# gps_car_v7.net
KiCad netlist of a schematic drawn in EAGLE
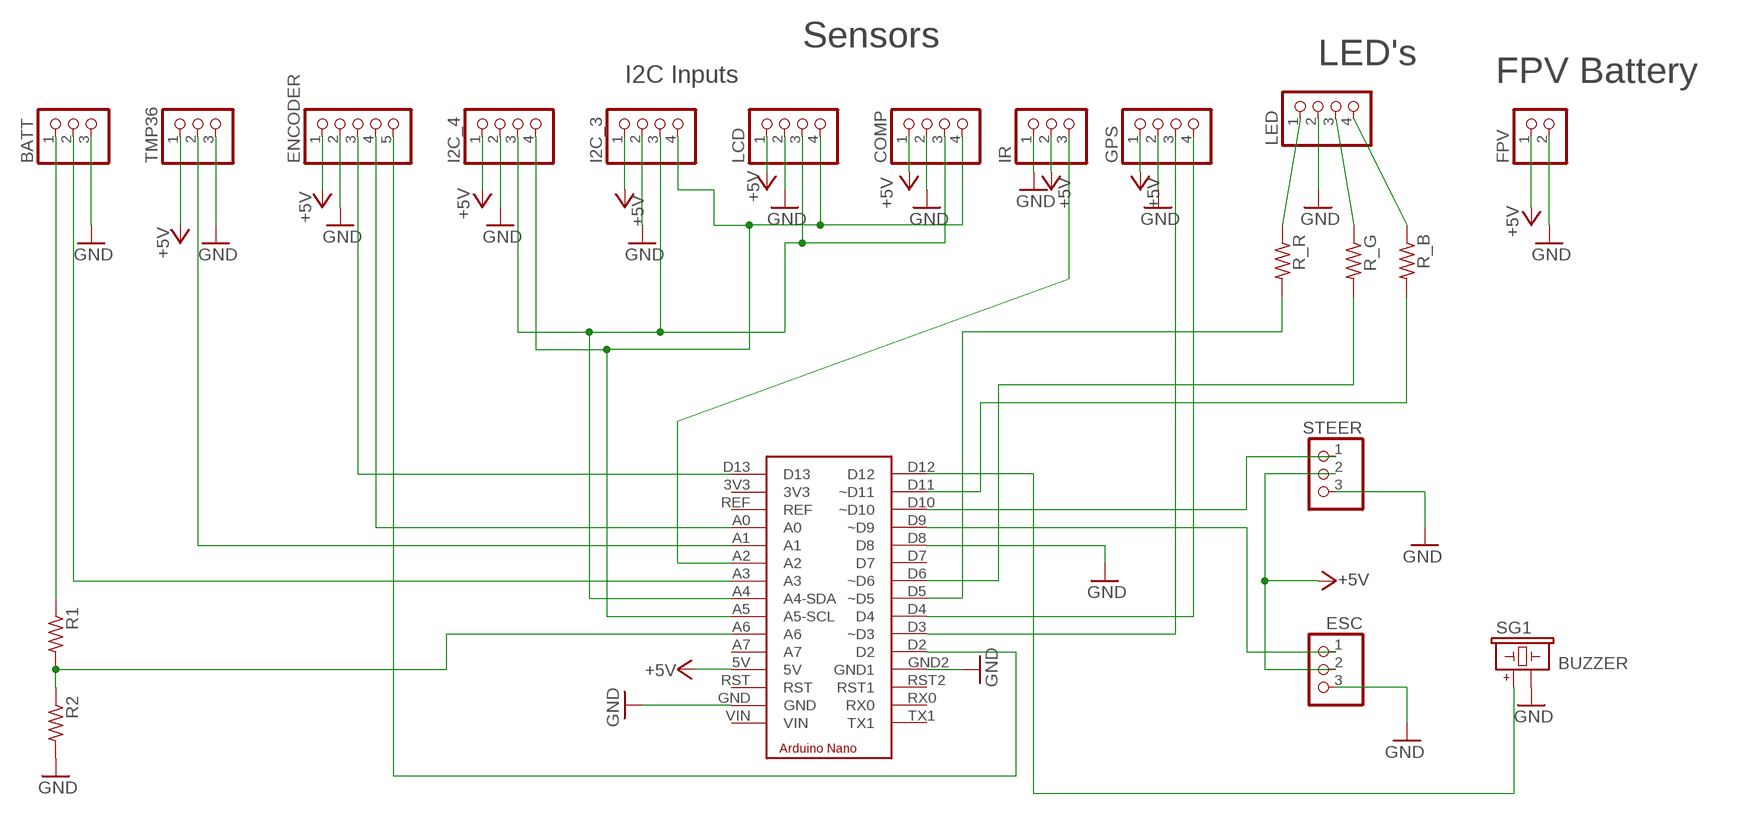
[diagram p0: schematic, sheet 1]

(export (version "E")
  (design (tool "Eeschema 10.0.6"))
  (components
    (comp (ref "BATT")
      (value "PINHD-1X3")
      (footprint "eagle-import:1X03")
      (libsource (lib "eagle-import") (part "pinhead_small_PINHD-1X3"))
    )
    (comp (ref "COMP")
      (value "PINHD-1X4")
      (footprint "eagle-import:1X04")
      (libsource (lib "eagle-import") (part "PINHD-1X4"))
    )
    (comp (ref "ENCODER")
      (value "PINHD-1X5")
      (footprint "eagle-import:1X05")
      (libsource (lib "eagle-import") (part "PINHD-1X5"))
    )
    (comp (ref "ESC")
      (value "PINHD-1X3")
      (footprint "eagle-import:1X03")
      (libsource (lib "eagle-import") (part "PINHD-1X3"))
    )
    (comp (ref "FPV")
      (value "PINHD-1X2")
      (footprint "eagle-import:1X02")
      (libsource (lib "eagle-import") (part "PINHD-1X2"))
    )
    (comp (ref "GPS")
      (value "PINHD-1X4")
      (footprint "eagle-import:1X04")
      (libsource (lib "eagle-import") (part "PINHD-1X4"))
    )
    (comp (ref "I2C_3")
      (value "PINHD-1X4")
      (footprint "eagle-import:1X04")
      (libsource (lib "eagle-import") (part "PINHD-1X4"))
    )
    (comp (ref "I2C_4")
      (value "PINHD-1X4")
      (footprint "eagle-import:1X04")
      (libsource (lib "eagle-import") (part "PINHD-1X4"))
    )
    (comp (ref "IR")
      (value "PINHD-1X3")
      (footprint "eagle-import:1X03")
      (libsource (lib "eagle-import") (part "PINHD-1X3"))
    )
    (comp (ref "LCD")
      (value "PINHD-1X4")
      (footprint "eagle-import:1X04")
      (libsource (lib "eagle-import") (part "PINHD-1X4"))
    )
    (comp (ref "LED")
      (value "PINHD-1X41X04X2MM")
      (footprint "eagle-import:1_04X2MM")
      (libsource (lib "eagle-import") (part "PINHD-1X41X04X2MM"))
    )
    (comp (ref "R1")
      (value "R-US_0204/2V")
      (footprint "eagle-import:0204V")
      (libsource (lib "eagle-import") (part "R-US_0204/2V"))
    )
    (comp (ref "R2")
      (value "R-US_0204/2V")
      (footprint "eagle-import:0204V")
      (libsource (lib "eagle-import") (part "R-US_0204/2V"))
    )
    (comp (ref "R_B")
      (value "R-US_0204/2V")
      (footprint "eagle-import:0204V")
      (libsource (lib "eagle-import") (part "R-US_0204/2V"))
    )
    (comp (ref "R_G")
      (value "R-US_0204/2V")
      (footprint "eagle-import:0204V")
      (libsource (lib "eagle-import") (part "R-US_0204/2V"))
    )
    (comp (ref "R_R")
      (value "R-US_0204/2V")
      (footprint "eagle-import:0204V")
      (libsource (lib "eagle-import") (part "R-US_0204/2V"))
    )
    (comp (ref "SG1")
      (value "BUZZER")
      (footprint "eagle-import:BUZZER-9MM-PTH")
      (libsource (lib "eagle-import") (part "BUZZER"))
    )
    (comp (ref "STEER")
      (value "PINHD-1X3")
      (footprint "eagle-import:1X03")
      (libsource (lib "eagle-import") (part "PINHD-1X3"))
    )
    (comp (ref "TMP36")
      (value "PINHD-1X31X03/2MM")
      (footprint "eagle-import:1_03X2MM")
      (libsource (lib "eagle-import") (part "PINHD-1X31X03/2MM"))
    )
    (comp (ref "U$1")
      (value "NANO")
      (footprint "eagle-import:NANO")
      (libsource (lib "eagle-import") (part "NANO"))
    )
  )
  (nets
    (net (code "1") (name "+5V") (class "Default")
      (node (ref "COMP") (pin "1") (pinfunction "1_1") (pintype "passive"))
      (node (ref "ENCODER") (pin "1") (pinfunction "1_1") (pintype "passive"))
      (node (ref "ESC") (pin "2") (pinfunction "2_2") (pintype "passive"))
      (node (ref "FPV") (pin "1") (pinfunction "1_1") (pintype "passive"))
      (node (ref "GPS") (pin "1") (pinfunction "1_1") (pintype "passive"))
      (node (ref "I2C_3") (pin "1") (pinfunction "1_1") (pintype "passive"))
      (node (ref "I2C_4") (pin "1") (pinfunction "1_1") (pintype "passive"))
      (node (ref "IR") (pin "2") (pinfunction "2_2") (pintype "passive"))
      (node (ref "LCD") (pin "1") (pinfunction "1_1") (pintype "passive"))
      (node (ref "STEER") (pin "2") (pinfunction "2_2") (pintype "passive"))
      (node (ref "TMP36") (pin "1") (pinfunction "1_1") (pintype "passive"))
      (node (ref "U$1") (pin "5V") (pinfunction "5V_5V") (pintype "bidirectional"))
    )
    (net (code "2") (name "GND") (class "Default")
      (node (ref "BATT") (pin "3") (pinfunction "3_3") (pintype "passive"))
      (node (ref "COMP") (pin "2") (pinfunction "2_2") (pintype "passive"))
      (node (ref "ENCODER") (pin "2") (pinfunction "2_2") (pintype "passive"))
      (node (ref "ESC") (pin "3") (pinfunction "3_3") (pintype "passive"))
      (node (ref "FPV") (pin "2") (pinfunction "2_2") (pintype "passive"))
      (node (ref "GPS") (pin "2") (pinfunction "2_2") (pintype "passive"))
      (node (ref "I2C_3") (pin "2") (pinfunction "2_2") (pintype "passive"))
      (node (ref "I2C_4") (pin "2") (pinfunction "2_2") (pintype "passive"))
      (node (ref "IR") (pin "1") (pinfunction "1_1") (pintype "passive"))
      (node (ref "LCD") (pin "2") (pinfunction "2_2") (pintype "passive"))
      (node (ref "LED") (pin "2") (pinfunction "2_2") (pintype "passive"))
      (node (ref "R2") (pin "2") (pinfunction "2_2") (pintype "passive"))
      (node (ref "SG1") (pin "P$2") (pinfunction "2_P$2") (pintype "passive"))
      (node (ref "STEER") (pin "3") (pinfunction "3_3") (pintype "passive"))
      (node (ref "TMP36") (pin "3") (pinfunction "3_3") (pintype "passive"))
      (node (ref "U$1") (pin "D8") (pinfunction "D8_D8") (pintype "bidirectional"))
      (node (ref "U$1") (pin "GND") (pinfunction "GND_GND") (pintype "bidirectional"))
      (node (ref "U$1") (pin "GND2") (pinfunction "GND1_GND2") (pintype "bidirectional"))
    )
    (net (code "3") (name "Net-(BATT-Pad1)") (class "Default")
      (node (ref "BATT") (pin "1") (pinfunction "1_1") (pintype "passive"))
      (node (ref "R1") (pin "1") (pinfunction "1_1") (pintype "passive"))
    )
    (net (code "4") (name "Net-(BATT-Pad2)") (class "Default")
      (node (ref "BATT") (pin "2") (pinfunction "2_2") (pintype "passive"))
      (node (ref "U$1") (pin "A3") (pinfunction "A3_A3") (pintype "bidirectional"))
    )
    (net (code "5") (name "Net-(ENCODER-Pad3)") (class "Default")
      (node (ref "ENCODER") (pin "3") (pinfunction "3_3") (pintype "passive"))
      (node (ref "U$1") (pin "D13") (pinfunction "D13_D13") (pintype "bidirectional"))
    )
    (net (code "6") (name "Net-(ENCODER-Pad4)") (class "Default")
      (node (ref "ENCODER") (pin "4") (pinfunction "4_4") (pintype "passive"))
      (node (ref "U$1") (pin "A0") (pinfunction "A0_A0") (pintype "bidirectional"))
    )
    (net (code "7") (name "Net-(ENCODER-Pad5)") (class "Default")
      (node (ref "ENCODER") (pin "5") (pinfunction "5_5") (pintype "passive"))
      (node (ref "U$1") (pin "D2") (pinfunction "D2_D2") (pintype "bidirectional"))
    )
    (net (code "8") (name "Net-(GPS-Pad4)") (class "Default")
      (node (ref "GPS") (pin "4") (pinfunction "4_4") (pintype "passive"))
      (node (ref "U$1") (pin "D4") (pinfunction "D4_D4") (pintype "bidirectional"))
    )
    (net (code "9") (name "Net-(IR-Pad3)") (class "Default")
      (node (ref "IR") (pin "3") (pinfunction "3_3") (pintype "passive"))
      (node (ref "U$1") (pin "A2") (pinfunction "A2_A2") (pintype "bidirectional"))
    )
    (net (code "10") (name "Net-(LED-Pad1)") (class "Default")
      (node (ref "LED") (pin "1") (pinfunction "1_1") (pintype "passive"))
      (node (ref "R_R") (pin "1") (pinfunction "1_1") (pintype "passive"))
    )
    (net (code "11") (name "Net-(LED-Pad3)") (class "Default")
      (node (ref "LED") (pin "3") (pinfunction "3_3") (pintype "passive"))
      (node (ref "R_G") (pin "1") (pinfunction "1_1") (pintype "passive"))
    )
    (net (code "12") (name "Net-(LED-Pad4)") (class "Default")
      (node (ref "LED") (pin "4") (pinfunction "4_4") (pintype "passive"))
      (node (ref "R_B") (pin "1") (pinfunction "1_1") (pintype "passive"))
    )
    (net (code "13") (name "Net-(R1-Pad2)") (class "Default")
      (node (ref "R1") (pin "2") (pinfunction "2_2") (pintype "passive"))
      (node (ref "R2") (pin "1") (pinfunction "1_1") (pintype "passive"))
      (node (ref "U$1") (pin "A6") (pinfunction "A6_A6") (pintype "bidirectional"))
    )
    (net (code "14") (name "Net-(SG1-1)") (class "Default")
      (node (ref "SG1") (pin "P$1") (pinfunction "1_P$1") (pintype "passive"))
      (node (ref "U$1") (pin "D12") (pinfunction "D12_D12") (pintype "bidirectional"))
    )
    (net (code "15") (name "Net-(TMP36-Pad2)") (class "Default")
      (node (ref "TMP36") (pin "2") (pinfunction "2_2") (pintype "passive"))
      (node (ref "U$1") (pin "A1") (pinfunction "A1_A1") (pintype "bidirectional"))
    )
    (net (code "16") (name "Net-(U$1-A4-SDA)") (class "Default")
      (node (ref "COMP") (pin "3") (pinfunction "3_3") (pintype "passive"))
      (node (ref "I2C_3") (pin "3") (pinfunction "3_3") (pintype "passive"))
      (node (ref "I2C_4") (pin "3") (pinfunction "3_3") (pintype "passive"))
      (node (ref "LCD") (pin "3") (pinfunction "3_3") (pintype "passive"))
      (node (ref "U$1") (pin "A4") (pinfunction "A4-SDA_A4") (pintype "bidirectional"))
    )
    (net (code "17") (name "Net-(U$1-A5-SCL)") (class "Default")
      (node (ref "COMP") (pin "4") (pinfunction "4_4") (pintype "passive"))
      (node (ref "I2C_3") (pin "4") (pinfunction "4_4") (pintype "passive"))
      (node (ref "I2C_4") (pin "4") (pinfunction "4_4") (pintype "passive"))
      (node (ref "LCD") (pin "4") (pinfunction "4_4") (pintype "passive"))
      (node (ref "U$1") (pin "A5") (pinfunction "A5-SCL_A5") (pintype "bidirectional"))
    )
    (net (code "18") (name "Net-(U$1-~{D3})") (class "Default")
      (node (ref "GPS") (pin "3") (pinfunction "3_3") (pintype "passive"))
      (node (ref "U$1") (pin "D3") (pinfunction "~{D3}_D3") (pintype "bidirectional"))
    )
    (net (code "19") (name "Net-(U$1-~{D5})") (class "Default")
      (node (ref "R_R") (pin "2") (pinfunction "2_2") (pintype "passive"))
      (node (ref "U$1") (pin "D5") (pinfunction "~{D5}_D5") (pintype "bidirectional"))
    )
    (net (code "20") (name "Net-(U$1-~{D6})") (class "Default")
      (node (ref "R_G") (pin "2") (pinfunction "2_2") (pintype "passive"))
      (node (ref "U$1") (pin "D6") (pinfunction "~{D6}_D6") (pintype "bidirectional"))
    )
    (net (code "21") (name "Net-(U$1-~{D9})") (class "Default")
      (node (ref "ESC") (pin "1") (pinfunction "1_1") (pintype "passive"))
      (node (ref "U$1") (pin "D9") (pinfunction "~{D9}_D9") (pintype "bidirectional"))
    )
    (net (code "22") (name "Net-(U$1-~{D10})") (class "Default")
      (node (ref "STEER") (pin "1") (pinfunction "1_1") (pintype "passive"))
      (node (ref "U$1") (pin "D10") (pinfunction "~{D10}_D10") (pintype "bidirectional"))
    )
    (net (code "23") (name "Net-(U$1-~{D11})") (class "Default")
      (node (ref "R_B") (pin "2") (pinfunction "2_2") (pintype "passive"))
      (node (ref "U$1") (pin "D11") (pinfunction "~{D11}_D11") (pintype "bidirectional"))
    )
    (net (code "24") (name "unconnected-(U$1-Pad3V3)") (class "Default")
      (node (ref "U$1") (pin "3V3") (pinfunction "3V3_3V3") (pintype "bidirectional"))
    )
    (net (code "25") (name "unconnected-(U$1-PadA7)") (class "Default")
      (node (ref "U$1") (pin "A7") (pinfunction "A7_A7") (pintype "bidirectional"))
    )
    (net (code "26") (name "unconnected-(U$1-PadD7)") (class "Default")
      (node (ref "U$1") (pin "D7") (pinfunction "D7_D7") (pintype "bidirectional"))
    )
    (net (code "27") (name "unconnected-(U$1-PadREF)") (class "Default")
      (node (ref "U$1") (pin "REF") (pinfunction "REF_REF") (pintype "bidirectional"))
    )
    (net (code "28") (name "unconnected-(U$1-PadRST)") (class "Default")
      (node (ref "U$1") (pin "RST") (pinfunction "RST_RST") (pintype "bidirectional"))
    )
    (net (code "29") (name "unconnected-(U$1-PadRX0)") (class "Default")
      (node (ref "U$1") (pin "RX0") (pinfunction "RX0_RX0") (pintype "bidirectional"))
    )
    (net (code "30") (name "unconnected-(U$1-PadTX1)") (class "Default")
      (node (ref "U$1") (pin "TX1") (pinfunction "TX1_TX1") (pintype "bidirectional"))
    )
    (net (code "31") (name "unconnected-(U$1-PadVIN)") (class "Default")
      (node (ref "U$1") (pin "VIN") (pinfunction "VIN_VIN") (pintype "bidirectional"))
    )
    (net (code "32") (name "unconnected-(U$1-RST1-PadRST2)") (class "Default")
      (node (ref "U$1") (pin "RST2") (pinfunction "RST1_RST2") (pintype "bidirectional"))
    )
  )
)
